# CH32H417WEU6-R0.net
KiCad netlist of a schematic drawn in Altium Designer
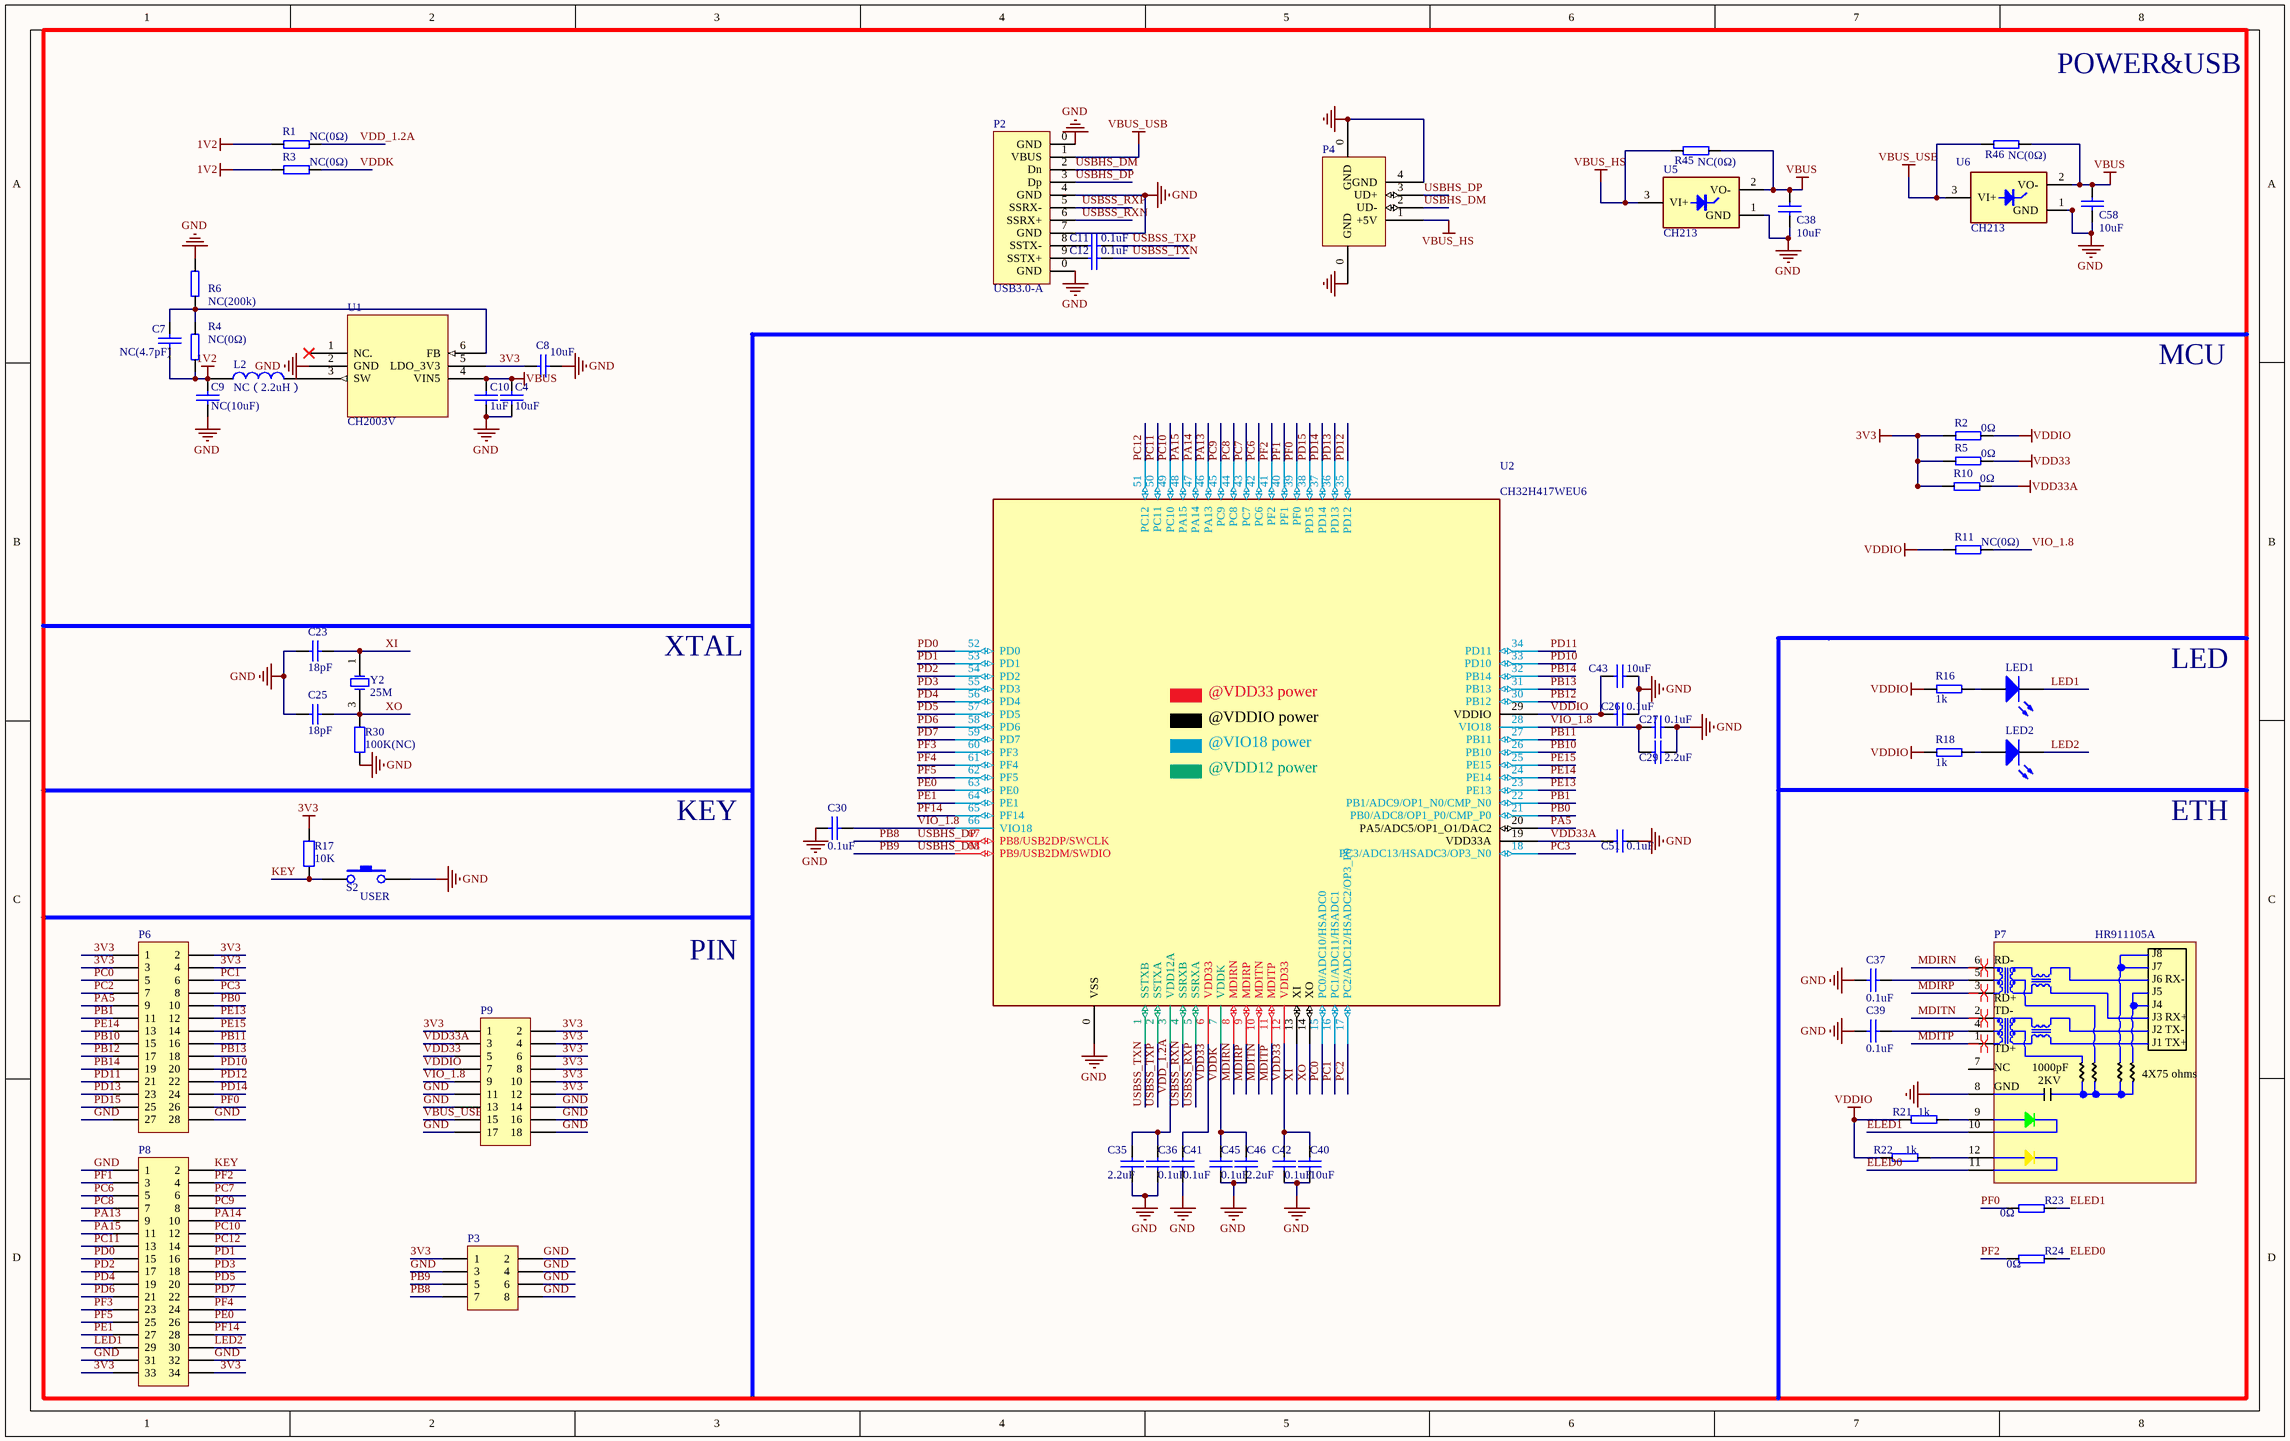
[diagram p0: CH32H417WEU6-R0.SchDoc]

(export (version "E")
  (design (tool "Eeschema 10.0.6"))
  (components
    (comp (ref "C4")
      (value "10uF")
      (footprint "0603_C")
      (description "Capacitor")
      (libsource (lib "*") (part "CAP"))
    )
    (comp (ref "C7")
      (value "NC(4.7pF)")
      (footprint "0402_C")
      (description "Capacitor")
      (libsource (lib "") (part "CAP_2"))
    )
    (comp (ref "C8")
      (value "10uF")
      (footprint "0603_C")
      (description "Capacitor")
      (libsource (lib "*") (part "CAP"))
    )
    (comp (ref "C9")
      (value "NC(10uF)")
      (footprint "0603_C")
      (description "Capacitor")
      (libsource (lib "*") (part "CAP"))
    )
    (comp (ref "C10")
      (value "1uF")
      (footprint "0402_C")
      (description "Capacitor")
      (libsource (lib "") (part "CAP_2"))
    )
    (comp (ref "C11")
      (value "0.1uF")
      (footprint "0402_C")
      (description "Capacitor")
      (libsource (lib "*") (part "CAP"))
    )
    (comp (ref "C12")
      (value "0.1uF")
      (footprint "0402_C")
      (description "Capacitor")
      (libsource (lib "*") (part "CAP"))
    )
    (comp (ref "C23")
      (value "18pF")
      (footprint "0402_C")
      (description "Capacitor")
      (libsource (lib "Miscellaneous Devices") (part "Cap"))
    )
    (comp (ref "C25")
      (value "18pF")
      (footprint "0402_C")
      (description "Capacitor")
      (libsource (lib "Miscellaneous Devices") (part "Cap"))
    )
    (comp (ref "C26")
      (value "0.1uF")
      (footprint "0402_C")
      (description "Capacitor")
      (libsource (lib "*") (part "CAP"))
    )
    (comp (ref "C27")
      (value "0.1uF")
      (footprint "0402_C")
      (description "Capacitor")
      (libsource (lib "*") (part "CAP"))
    )
    (comp (ref "C29")
      (value "2.2uF")
      (footprint "0402_C")
      (description "Capacitor")
      (libsource (lib "*") (part "CAP"))
    )
    (comp (ref "C30")
      (value "0.1uF")
      (footprint "0402_C")
      (description "Capacitor")
      (libsource (lib "*") (part "CAP"))
    )
    (comp (ref "C35")
      (value "2.2uF")
      (footprint "0402_C")
      (description "Capacitor")
      (libsource (lib "*") (part "CAP"))
    )
    (comp (ref "C36")
      (value "0.1uF")
      (footprint "0402_C")
      (description "Capacitor")
      (libsource (lib "*") (part "CAP"))
    )
    (comp (ref "C37")
      (value "0.1uF")
      (footprint "0402_C")
      (description "Capacitor")
      (libsource (lib "wch_sch_others") (part "CAP"))
    )
    (comp (ref "C38")
      (value "10uF")
      (footprint "0603_C")
      (description "Capacitor")
      (libsource (lib "") (part "CAP_1"))
    )
    (comp (ref "C39")
      (value "0.1uF")
      (footprint "0402_C")
      (description "Capacitor")
      (libsource (lib "wch_sch_others") (part "CAP"))
    )
    (comp (ref "C40")
      (value "10uF")
      (footprint "0402_C")
      (description "Capacitor")
      (libsource (lib "*") (part "CAP"))
    )
    (comp (ref "C41")
      (value "0.1uF")
      (footprint "0402_C")
      (description "Capacitor")
      (libsource (lib "*") (part "CAP"))
    )
    (comp (ref "C42")
      (value "0.1uF")
      (footprint "0402_C")
      (description "Capacitor")
      (libsource (lib "*") (part "CAP"))
    )
    (comp (ref "C43")
      (value "10uF")
      (footprint "0402_C")
      (description "Capacitor")
      (libsource (lib "*") (part "CAP"))
    )
    (comp (ref "C45")
      (value "0.1uF")
      (footprint "0402_C")
      (description "Capacitor")
      (libsource (lib "*") (part "CAP"))
    )
    (comp (ref "C46")
      (value "2.2uF")
      (footprint "0402_C")
      (description "Capacitor")
      (libsource (lib "*") (part "CAP"))
    )
    (comp (ref "C51")
      (value "0.1uF")
      (footprint "0402_C")
      (description "Capacitor")
      (libsource (lib "*") (part "CAP"))
    )
    (comp (ref "C58")
      (value "10uF")
      (footprint "0603_C")
      (description "Capacitor")
      (libsource (lib "") (part "CAP_1"))
    )
    (comp (ref "L2") (value "NC（2.2uH）") (footprint "CD32") (libsource (lib "*") (part "INDUCTOR")))
    (comp (ref "LED1")
      (value "LED2  blue")
      (footprint "0603+")
      (description "Typical INFRARED GaAs LED")
      (fields (field (name "PUBLISHER") "Altium Limited"))
      (libsource (lib "Miscellaneous Devices") (part "LED0"))
    )
    (comp (ref "LED2")
      (value "LED1   blue")
      (footprint "0603+")
      (description "Typical INFRARED GaAs LED")
      (fields (field (name "PUBLISHER") "Altium Limited"))
      (libsource (lib "Miscellaneous Devices") (part "LED0"))
    )
    (comp (ref "P2")
      (value "USB3.0-A")
      (footprint "USB3.0-A-Receptacle")
      (libsource (lib "wch_sch_others") (part "USB3.0-A"))
    )
    (comp (ref "P3")
      (value "HEADER 4x2")
      (footprint "MYPCB:IDC8-2.54mm")
      (description "Header, 4-Pin, Dual row")
      (libsource (lib "wch_sch_others") (part "HEADER 4x2"))
    )
    (comp (ref "P4")
      (value "USB_A")
      (footprint "USBAF")
      (description "USB Port")
      (libsource (lib "*") (part "USB"))
    )
    (comp (ref "P6")
      (value "HEADER 14x2")
      (footprint "MYPCB:IDC28-2.54MM")
      (description "Header, 14-Pin, Dual row")
      (libsource (lib "wch_sch_others") (part "HEADER 14x2"))
    )
    (comp (ref "P7") (value "HR911105A") (footprint "HR911105A") (libsource (lib "*") (part "HR911105A")))
    (comp (ref "P8")
      (value "HEADER 17x2")
      (footprint "MYPCB:IDC34-2.54MM")
      (description "Header, 17-Pin, Dual row")
      (libsource (lib "wch_sch_others") (part "HEADER 17x2"))
    )
    (comp (ref "P9")
      (value "HEADER 9x2")
      (footprint "MYPCB:IDC18-2.54MM")
      (description "Header, 9-Pin, Dual row")
      (libsource (lib "wch_sch_others") (part "HEADER 9x2"))
    )
    (comp (ref "R1") (value "NC(0Ω)") (footprint "0402") (libsource (lib "wch_sch_others") (part "RES")))
    (comp (ref "R2") (value "0Ω") (footprint "0402") (libsource (lib "wch_sch_others") (part "RES")))
    (comp (ref "R3") (value "NC(0Ω)") (footprint "0402") (libsource (lib "wch_sch_others") (part "RES")))
    (comp (ref "R4") (value "NC(0Ω)") (footprint "0402") (libsource (lib "wch_sch_others") (part "RES")))
    (comp (ref "R5") (value "0Ω") (footprint "0402") (libsource (lib "wch_sch_others") (part "RES")))
    (comp (ref "R6") (value "NC(200k)") (footprint "0402") (libsource (lib "wch_sch_others") (part "RES")))
    (comp (ref "R10") (value "0Ω") (footprint "0402") (libsource (lib "wch_sch_others") (part "RES")))
    (comp (ref "R11") (value "NC(0Ω)") (footprint "0402") (libsource (lib "wch_sch_others") (part "RES")))
    (comp (ref "R16") (value "1k") (footprint "0402") (libsource (lib "wch_sch_others") (part "RES")))
    (comp (ref "R17")
      (value "10K")
      (footprint "0402")
      (description "Resistor")
      (libsource (lib "Miscellaneous Devices") (part "Res2"))
    )
    (comp (ref "R18") (value "1k") (footprint "0402") (libsource (lib "wch_sch_others") (part "RES")))
    (comp (ref "R21") (value "1k") (footprint "0402") (libsource (lib "") (part "RES_1")))
    (comp (ref "R22") (value "1k") (footprint "0402") (libsource (lib "") (part "RES_1")))
    (comp (ref "R23") (value "0Ω") (footprint "0402") (libsource (lib "") (part "RES_1")))
    (comp (ref "R24") (value "0Ω") (footprint "0402") (libsource (lib "") (part "RES_1")))
    (comp (ref "R30")
      (value "100K(NC)")
      (footprint "0402")
      (description "Resistor")
      (libsource (lib "") (part "Res2_1"))
    )
    (comp (ref "R45") (value "NC(0Ω)") (footprint "0402") (libsource (lib "") (part "RES_1")))
    (comp (ref "R46") (value "NC(0Ω)") (footprint "0402") (libsource (lib "") (part "RES_1")))
    (comp (ref "S2")
      (value "USER")
      (footprint "SMD_6.1x3.65x2.5mm-KEY")
      (libsource (lib "wch_sch_others") (part "KEY1"))
    )
    (comp (ref "U1")
      (value "CH2003V")
      (footprint "SOT-23-6")
      (description "Step-Down DC-DC Converter, 5V input, FB 0.6V, 800mA output, with LDO 3.3V * 200mA")
      (libsource (lib "DHXXXSCH") (part "CH2003K"))
    )
    (comp (ref "U2")
      (value "CH32H417WEU6")
      (footprint "QFN68_8X8")
      (description "RISC-V FPU HD-MCU, 400MHz, USB3.0, 100M Ethernet, DVP, SDMMC, QSPI, OPA, ADC, DAC")
      (libsource (lib "DHXXXSCH") (part "CH32H417WEU6"))
    )
    (comp (ref "U5")
      (value "CH213")
      (footprint "SOT-23-3")
      (description "Ideal Diode 5V*1A")
      (libsource (lib "CHXXX") (part "CH213E"))
    )
    (comp (ref "U6")
      (value "CH213")
      (footprint "SOT-23-3")
      (description "Ideal Diode 5V*1A")
      (libsource (lib "CHXXX") (part "CH213E"))
    )
    (comp (ref "Y2")
      (value "25M")
      (footprint "XT3225")
      (description "Crystal Oscillator")
      (fields (field (name "PUBLISHER") "Altium Limited"))
      (libsource (lib "Miscellaneous Devices") (part "XTAL"))
    )
  )
  (nets
    (net (code "1") (name "/ELED0") (class "Default")
      (node (ref "P7") (pin "11") (pintype "passive"))
      (node (ref "R24") (pin "2") (pintype "passive"))
    )
    (net (code "2") (name "/ELED1") (class "Default")
      (node (ref "P7") (pin "10") (pintype "passive"))
      (node (ref "R23") (pin "2") (pintype "passive"))
    )
    (net (code "3") (name "/KEY") (class "Default")
      (node (ref "P8") (pin "2") (pinfunction "2_2") (pintype "passive"))
      (node (ref "R17") (pin "2") (pinfunction "2_2") (pintype "passive"))
      (node (ref "S2") (pin "1") (pinfunction "1_1") (pintype "passive"))
    )
    (net (code "4") (name "/LED1") (class "Default")
      (node (ref "LED1") (pin "2") (pinfunction "K_2") (pintype "passive"))
      (node (ref "P8") (pin "29") (pinfunction "29_29") (pintype "passive"))
    )
    (net (code "5") (name "/LED2") (class "Default")
      (node (ref "LED2") (pin "2") (pinfunction "K_2") (pintype "passive"))
      (node (ref "P8") (pin "30") (pinfunction "30_30") (pintype "passive"))
    )
    (net (code "6") (name "/MDIRN") (class "Default")
      (node (ref "P7") (pin "6") (pintype "passive"))
      (node (ref "U2") (pin "8") (pinfunction "MDIRN_8") (pintype "bidirectional"))
    )
    (net (code "7") (name "/MDIRP") (class "Default")
      (node (ref "P7") (pin "3") (pintype "passive"))
      (node (ref "U2") (pin "9") (pinfunction "MDIRP_9") (pintype "bidirectional"))
    )
    (net (code "8") (name "/MDITN") (class "Default")
      (node (ref "P7") (pin "2") (pintype "passive"))
      (node (ref "U2") (pin "10") (pinfunction "MDITN_10") (pintype "bidirectional"))
    )
    (net (code "9") (name "/MDITP") (class "Default")
      (node (ref "P7") (pin "1") (pintype "passive"))
      (node (ref "U2") (pin "11") (pinfunction "MDITP_11") (pintype "bidirectional"))
    )
    (net (code "10") (name "/PA5") (class "Default")
      (node (ref "P6") (pin "9") (pinfunction "9_9") (pintype "passive"))
      (node (ref "U2") (pin "20") (pinfunction "PA5/ADC5/OP1_O1/DAC2_20") (pintype "bidirectional"))
    )
    (net (code "11") (name "/PA13") (class "Default")
      (node (ref "P8") (pin "9") (pinfunction "9_9") (pintype "passive"))
      (node (ref "U2") (pin "46") (pinfunction "PA13_46") (pintype "bidirectional"))
    )
    (net (code "12") (name "/PA14") (class "Default")
      (node (ref "P8") (pin "10") (pinfunction "10_10") (pintype "passive"))
      (node (ref "U2") (pin "47") (pinfunction "PA14_47") (pintype "bidirectional"))
    )
    (net (code "13") (name "/PA15") (class "Default")
      (node (ref "P8") (pin "11") (pinfunction "11_11") (pintype "passive"))
      (node (ref "U2") (pin "48") (pinfunction "PA15_48") (pintype "bidirectional"))
    )
    (net (code "14") (name "/PB0") (class "Default")
      (node (ref "P6") (pin "10") (pinfunction "10_10") (pintype "passive"))
      (node (ref "U2") (pin "21") (pinfunction "PB0/ADC8/OP1_P0/CMP_P0_21") (pintype "bidirectional"))
    )
    (net (code "15") (name "/PB1") (class "Default")
      (node (ref "P6") (pin "11") (pinfunction "11_11") (pintype "passive"))
      (node (ref "U2") (pin "22") (pinfunction "PB1/ADC9/OP1_N0/CMP_N0_22") (pintype "bidirectional"))
    )
    (net (code "16") (name "/PB8") (class "Default")
      (node (ref "P2") (pin "3") (pinfunction "Dp_3") (pintype "passive"))
      (node (ref "P3") (pin "7") (pinfunction "7_7") (pintype "passive"))
      (node (ref "P4") (pin "3") (pinfunction "UD+_3") (pintype "bidirectional"))
      (node (ref "U2") (pin "67") (pinfunction "PB8/USB2DP/SWCLK_67") (pintype "bidirectional"))
    )
    (net (code "17") (name "/PB9") (class "Default")
      (node (ref "P2") (pin "2") (pinfunction "Dn_2") (pintype "passive"))
      (node (ref "P3") (pin "5") (pinfunction "5_5") (pintype "passive"))
      (node (ref "P4") (pin "2") (pinfunction "UD-_2") (pintype "bidirectional"))
      (node (ref "U2") (pin "68") (pinfunction "PB9/USB2DM/SWDIO_68") (pintype "bidirectional"))
    )
    (net (code "18") (name "/PB10") (class "Default")
      (node (ref "P6") (pin "15") (pinfunction "15_15") (pintype "passive"))
      (node (ref "U2") (pin "26") (pinfunction "PB10_26") (pintype "bidirectional"))
    )
    (net (code "19") (name "/PB11") (class "Default")
      (node (ref "P6") (pin "16") (pinfunction "16_16") (pintype "passive"))
      (node (ref "U2") (pin "27") (pinfunction "PB11_27") (pintype "bidirectional"))
    )
    (net (code "20") (name "/PB12") (class "Default")
      (node (ref "P6") (pin "17") (pinfunction "17_17") (pintype "passive"))
      (node (ref "U2") (pin "30") (pinfunction "PB12_30") (pintype "bidirectional"))
    )
    (net (code "21") (name "/PB13") (class "Default")
      (node (ref "P6") (pin "18") (pinfunction "18_18") (pintype "passive"))
      (node (ref "U2") (pin "31") (pinfunction "PB13_31") (pintype "bidirectional"))
    )
    (net (code "22") (name "/PB14") (class "Default")
      (node (ref "P6") (pin "19") (pinfunction "19_19") (pintype "passive"))
      (node (ref "U2") (pin "32") (pinfunction "PB14_32") (pintype "bidirectional"))
    )
    (net (code "23") (name "/PC0") (class "Default")
      (node (ref "P6") (pin "5") (pinfunction "5_5") (pintype "passive"))
      (node (ref "U2") (pin "15") (pinfunction "PC0/ADC10/HSADC0_15") (pintype "bidirectional"))
    )
    (net (code "24") (name "/PC1") (class "Default")
      (node (ref "P6") (pin "6") (pinfunction "6_6") (pintype "passive"))
      (node (ref "U2") (pin "16") (pinfunction "PC1/ADC11/HSADC1_16") (pintype "bidirectional"))
    )
    (net (code "25") (name "/PC2") (class "Default")
      (node (ref "P6") (pin "7") (pinfunction "7_7") (pintype "passive"))
      (node (ref "U2") (pin "17") (pinfunction "PC2/ADC12/HSADC2/OP3_P0_17") (pintype "bidirectional"))
    )
    (net (code "26") (name "/PC3") (class "Default")
      (node (ref "P6") (pin "8") (pinfunction "8_8") (pintype "passive"))
      (node (ref "U2") (pin "18") (pinfunction "PC3/ADC13/HSADC3/OP3_N0_18") (pintype "bidirectional"))
    )
    (net (code "27") (name "/PC6") (class "Default")
      (node (ref "P8") (pin "5") (pinfunction "5_5") (pintype "passive"))
      (node (ref "U2") (pin "42") (pinfunction "PC6_42") (pintype "bidirectional"))
    )
    (net (code "28") (name "/PC7") (class "Default")
      (node (ref "P8") (pin "6") (pinfunction "6_6") (pintype "passive"))
      (node (ref "U2") (pin "43") (pinfunction "PC7_43") (pintype "bidirectional"))
    )
    (net (code "29") (name "/PC8") (class "Default")
      (node (ref "P8") (pin "7") (pinfunction "7_7") (pintype "passive"))
      (node (ref "U2") (pin "44") (pinfunction "PC8_44") (pintype "bidirectional"))
    )
    (net (code "30") (name "/PC9") (class "Default")
      (node (ref "P8") (pin "8") (pinfunction "8_8") (pintype "passive"))
      (node (ref "U2") (pin "45") (pinfunction "PC9_45") (pintype "bidirectional"))
    )
    (net (code "31") (name "/PC10") (class "Default")
      (node (ref "P8") (pin "12") (pinfunction "12_12") (pintype "passive"))
      (node (ref "U2") (pin "49") (pinfunction "PC10_49") (pintype "bidirectional"))
    )
    (net (code "32") (name "/PC11") (class "Default")
      (node (ref "P8") (pin "13") (pinfunction "13_13") (pintype "passive"))
      (node (ref "U2") (pin "50") (pinfunction "PC11_50") (pintype "bidirectional"))
    )
    (net (code "33") (name "/PC12") (class "Default")
      (node (ref "P8") (pin "14") (pinfunction "14_14") (pintype "passive"))
      (node (ref "U2") (pin "51") (pinfunction "PC12_51") (pintype "bidirectional"))
    )
    (net (code "34") (name "/PD0") (class "Default")
      (node (ref "P8") (pin "15") (pinfunction "15_15") (pintype "passive"))
      (node (ref "U2") (pin "52") (pinfunction "PD0_52") (pintype "bidirectional"))
    )
    (net (code "35") (name "/PD1") (class "Default")
      (node (ref "P8") (pin "16") (pinfunction "16_16") (pintype "passive"))
      (node (ref "U2") (pin "53") (pinfunction "PD1_53") (pintype "bidirectional"))
    )
    (net (code "36") (name "/PD2") (class "Default")
      (node (ref "P8") (pin "17") (pinfunction "17_17") (pintype "passive"))
      (node (ref "U2") (pin "54") (pinfunction "PD2_54") (pintype "bidirectional"))
    )
    (net (code "37") (name "/PD3") (class "Default")
      (node (ref "P8") (pin "18") (pinfunction "18_18") (pintype "passive"))
      (node (ref "U2") (pin "55") (pinfunction "PD3_55") (pintype "bidirectional"))
    )
    (net (code "38") (name "/PD4") (class "Default")
      (node (ref "P8") (pin "19") (pinfunction "19_19") (pintype "passive"))
      (node (ref "U2") (pin "56") (pinfunction "PD4_56") (pintype "bidirectional"))
    )
    (net (code "39") (name "/PD5") (class "Default")
      (node (ref "P8") (pin "20") (pinfunction "20_20") (pintype "passive"))
      (node (ref "U2") (pin "57") (pinfunction "PD5_57") (pintype "bidirectional"))
    )
    (net (code "40") (name "/PD6") (class "Default")
      (node (ref "P8") (pin "21") (pinfunction "21_21") (pintype "passive"))
      (node (ref "U2") (pin "58") (pinfunction "PD6_58") (pintype "bidirectional"))
    )
    (net (code "41") (name "/PD7") (class "Default")
      (node (ref "P8") (pin "22") (pinfunction "22_22") (pintype "passive"))
      (node (ref "U2") (pin "59") (pinfunction "PD7_59") (pintype "bidirectional"))
    )
    (net (code "42") (name "/PD10") (class "Default")
      (node (ref "P6") (pin "20") (pinfunction "20_20") (pintype "passive"))
      (node (ref "U2") (pin "33") (pinfunction "PD10_33") (pintype "bidirectional"))
    )
    (net (code "43") (name "/PD11") (class "Default")
      (node (ref "P6") (pin "21") (pinfunction "21_21") (pintype "passive"))
      (node (ref "U2") (pin "34") (pinfunction "PD11_34") (pintype "bidirectional"))
    )
    (net (code "44") (name "/PD12") (class "Default")
      (node (ref "P6") (pin "22") (pinfunction "22_22") (pintype "passive"))
      (node (ref "U2") (pin "35") (pinfunction "PD12_35") (pintype "bidirectional"))
    )
    (net (code "45") (name "/PD13") (class "Default")
      (node (ref "P6") (pin "23") (pinfunction "23_23") (pintype "passive"))
      (node (ref "U2") (pin "36") (pinfunction "PD13_36") (pintype "bidirectional"))
    )
    (net (code "46") (name "/PD14") (class "Default")
      (node (ref "P6") (pin "24") (pinfunction "24_24") (pintype "passive"))
      (node (ref "U2") (pin "37") (pinfunction "PD14_37") (pintype "bidirectional"))
    )
    (net (code "47") (name "/PD15") (class "Default")
      (node (ref "P6") (pin "25") (pinfunction "25_25") (pintype "passive"))
      (node (ref "U2") (pin "38") (pinfunction "PD15_38") (pintype "bidirectional"))
    )
    (net (code "48") (name "/PE0") (class "Default")
      (node (ref "P8") (pin "26") (pinfunction "26_26") (pintype "passive"))
      (node (ref "U2") (pin "63") (pinfunction "PE0_63") (pintype "bidirectional"))
    )
    (net (code "49") (name "/PE1") (class "Default")
      (node (ref "P8") (pin "27") (pinfunction "27_27") (pintype "passive"))
      (node (ref "U2") (pin "64") (pinfunction "PE1_64") (pintype "bidirectional"))
    )
    (net (code "50") (name "/PE13") (class "Default")
      (node (ref "P6") (pin "12") (pinfunction "12_12") (pintype "passive"))
      (node (ref "U2") (pin "23") (pinfunction "PE13_23") (pintype "bidirectional"))
    )
    (net (code "51") (name "/PE14") (class "Default")
      (node (ref "P6") (pin "13") (pinfunction "13_13") (pintype "passive"))
      (node (ref "U2") (pin "24") (pinfunction "PE14_24") (pintype "bidirectional"))
    )
    (net (code "52") (name "/PE15") (class "Default")
      (node (ref "P6") (pin "14") (pinfunction "14_14") (pintype "passive"))
      (node (ref "U2") (pin "25") (pinfunction "PE15_25") (pintype "bidirectional"))
    )
    (net (code "53") (name "/PF0") (class "Default")
      (node (ref "P6") (pin "26") (pinfunction "26_26") (pintype "passive"))
      (node (ref "R23") (pin "1") (pintype "passive"))
      (node (ref "U2") (pin "39") (pinfunction "PF0_39") (pintype "bidirectional"))
    )
    (net (code "54") (name "/PF1") (class "Default")
      (node (ref "P8") (pin "3") (pinfunction "3_3") (pintype "passive"))
      (node (ref "U2") (pin "40") (pinfunction "PF1_40") (pintype "bidirectional"))
    )
    (net (code "55") (name "/PF2") (class "Default")
      (node (ref "P8") (pin "4") (pinfunction "4_4") (pintype "passive"))
      (node (ref "R24") (pin "1") (pintype "passive"))
      (node (ref "U2") (pin "41") (pinfunction "PF2_41") (pintype "bidirectional"))
    )
    (net (code "56") (name "/PF3") (class "Default")
      (node (ref "P8") (pin "23") (pinfunction "23_23") (pintype "passive"))
      (node (ref "U2") (pin "60") (pinfunction "PF3_60") (pintype "bidirectional"))
    )
    (net (code "57") (name "/PF4") (class "Default")
      (node (ref "P8") (pin "24") (pinfunction "24_24") (pintype "passive"))
      (node (ref "U2") (pin "61") (pinfunction "PF4_61") (pintype "bidirectional"))
    )
    (net (code "58") (name "/PF5") (class "Default")
      (node (ref "P8") (pin "25") (pinfunction "25_25") (pintype "passive"))
      (node (ref "U2") (pin "62") (pinfunction "PF5_62") (pintype "bidirectional"))
    )
    (net (code "59") (name "/PF14") (class "Default")
      (node (ref "P8") (pin "28") (pinfunction "28_28") (pintype "passive"))
      (node (ref "U2") (pin "65") (pinfunction "PF14_65") (pintype "bidirectional"))
    )
    (net (code "60") (name "/USBSS_RXN") (class "Default")
      (node (ref "P2") (pin "6") (pinfunction "SSRX+_6") (pintype "passive"))
      (node (ref "U2") (pin "4") (pinfunction "SSRXB_4") (pintype "bidirectional"))
    )
    (net (code "61") (name "/USBSS_RXP") (class "Default")
      (node (ref "P2") (pin "5") (pinfunction "SSRX-_5") (pintype "passive"))
      (node (ref "U2") (pin "5") (pinfunction "SSRXA_5") (pintype "bidirectional"))
    )
    (net (code "62") (name "/USBSS_TXN") (class "Default")
      (node (ref "C12") (pin "2") (pinfunction "2_2") (pintype "passive"))
      (node (ref "U2") (pin "1") (pinfunction "SSTXB_1") (pintype "bidirectional"))
    )
    (net (code "63") (name "/USBSS_TXP") (class "Default")
      (node (ref "C11") (pin "2") (pinfunction "2_2") (pintype "passive"))
      (node (ref "U2") (pin "2") (pinfunction "SSTXA_2") (pintype "bidirectional"))
    )
    (net (code "64") (name "/VDDK") (class "Default")
      (node (ref "C45") (pin "2") (pinfunction "2_2") (pintype "passive"))
      (node (ref "C46") (pin "1") (pinfunction "1_1") (pintype "passive"))
      (node (ref "R3") (pin "1") (pintype "passive"))
      (node (ref "U2") (pin "7") (pinfunction "VDDK_7") (pintype "power_in"))
    )
    (net (code "65") (name "/VDD_1.2A") (class "Default")
      (node (ref "C35") (pin "2") (pinfunction "2_2") (pintype "passive"))
      (node (ref "C36") (pin "2") (pinfunction "2_2") (pintype "passive"))
      (node (ref "R1") (pin "1") (pintype "passive"))
      (node (ref "U2") (pin "3") (pinfunction "VDD12A_3") (pintype "power_in"))
    )
    (net (code "66") (name "/VIO_1.8") (class "Default")
      (node (ref "C27") (pin "1") (pinfunction "1_1") (pintype "passive"))
      (node (ref "C29") (pin "2") (pinfunction "2_2") (pintype "passive"))
      (node (ref "C30") (pin "1") (pinfunction "1_1") (pintype "passive"))
      (node (ref "P9") (pin "9") (pinfunction "9_9") (pintype "passive"))
      (node (ref "R11") (pin "1") (pintype "passive"))
      (node (ref "U2") (pin "28") (pinfunction "VIO18_28") (pintype "power_in"))
      (node (ref "U2") (pin "66") (pinfunction "VIO18_66") (pintype "power_in"))
    )
    (net (code "67") (name "/XI") (class "Default")
      (node (ref "C23") (pin "2") (pinfunction "2_2") (pintype "passive"))
      (node (ref "U2") (pin "13") (pinfunction "XI_13") (pintype "bidirectional"))
      (node (ref "Y2") (pin "1") (pinfunction "OSC1_1") (pintype "passive"))
    )
    (net (code "68") (name "/XO") (class "Default")
      (node (ref "C25") (pin "2") (pinfunction "2_2") (pintype "passive"))
      (node (ref "R30") (pin "2") (pinfunction "2_2") (pintype "passive"))
      (node (ref "U2") (pin "14") (pinfunction "XO_14") (pintype "bidirectional"))
      (node (ref "Y2") (pin "3") (pinfunction "OSC2_3") (pintype "passive"))
    )
    (net (code "69") (name "1V2") (class "Default")
      (node (ref "C7") (pin "1") (pinfunction "1_1") (pintype "passive"))
      (node (ref "C9") (pin "2") (pinfunction "2_2") (pintype "passive"))
      (node (ref "L2") (pin "2") (pinfunction "2_2") (pintype "passive"))
      (node (ref "R1") (pin "2") (pintype "passive"))
      (node (ref "R3") (pin "2") (pintype "passive"))
      (node (ref "R4") (pin "1") (pintype "passive"))
    )
    (net (code "70") (name "3V3") (class "Default")
      (node (ref "C8") (pin "2") (pinfunction "2_2") (pintype "passive"))
      (node (ref "P3") (pin "1") (pinfunction "1_1") (pintype "passive"))
      (node (ref "P6") (pin "1") (pinfunction "1_1") (pintype "passive"))
      (node (ref "P6") (pin "2") (pinfunction "2_2") (pintype "passive"))
      (node (ref "P6") (pin "3") (pinfunction "3_3") (pintype "passive"))
      (node (ref "P6") (pin "4") (pinfunction "4_4") (pintype "passive"))
      (node (ref "P8") (pin "33") (pinfunction "33_33") (pintype "passive"))
      (node (ref "P8") (pin "34") (pinfunction "34_34") (pintype "passive"))
      (node (ref "P9") (pin "1") (pinfunction "1_1") (pintype "passive"))
      (node (ref "P9") (pin "10") (pinfunction "10_10") (pintype "passive"))
      (node (ref "P9") (pin "12") (pinfunction "12_12") (pintype "passive"))
      (node (ref "P9") (pin "2") (pinfunction "2_2") (pintype "passive"))
      (node (ref "P9") (pin "4") (pinfunction "4_4") (pintype "passive"))
      (node (ref "P9") (pin "6") (pinfunction "6_6") (pintype "passive"))
      (node (ref "P9") (pin "8") (pinfunction "8_8") (pintype "passive"))
      (node (ref "R10") (pin "2") (pintype "passive"))
      (node (ref "R17") (pin "1") (pinfunction "1_1") (pintype "passive"))
      (node (ref "R2") (pin "2") (pintype "passive"))
      (node (ref "R5") (pin "2") (pintype "passive"))
      (node (ref "U1") (pin "5") (pinfunction "LDO_3V3_5") (pintype "power_in"))
    )
    (net (code "71") (name "GND") (class "Default")
      (node (ref "C10") (pin "1") (pinfunction "1_1") (pintype "passive"))
      (node (ref "C23") (pin "1") (pinfunction "1_1") (pintype "passive"))
      (node (ref "C25") (pin "1") (pinfunction "1_1") (pintype "passive"))
      (node (ref "C26") (pin "2") (pinfunction "2_2") (pintype "passive"))
      (node (ref "C27") (pin "2") (pinfunction "2_2") (pintype "passive"))
      (node (ref "C29") (pin "1") (pinfunction "1_1") (pintype "passive"))
      (node (ref "C30") (pin "2") (pinfunction "2_2") (pintype "passive"))
      (node (ref "C35") (pin "1") (pinfunction "1_1") (pintype "passive"))
      (node (ref "C36") (pin "1") (pinfunction "1_1") (pintype "passive"))
      (node (ref "C37") (pin "1") (pinfunction "1_1") (pintype "passive"))
      (node (ref "C38") (pin "2") (pinfunction "2_2") (pintype "passive"))
      (node (ref "C39") (pin "1") (pinfunction "1_1") (pintype "passive"))
      (node (ref "C4") (pin "1") (pinfunction "1_1") (pintype "passive"))
      (node (ref "C40") (pin "1") (pinfunction "1_1") (pintype "passive"))
      (node (ref "C41") (pin "1") (pinfunction "1_1") (pintype "passive"))
      (node (ref "C42") (pin "1") (pinfunction "1_1") (pintype "passive"))
      (node (ref "C43") (pin "1") (pinfunction "1_1") (pintype "passive"))
      (node (ref "C45") (pin "1") (pinfunction "1_1") (pintype "passive"))
      (node (ref "C46") (pin "2") (pinfunction "2_2") (pintype "passive"))
      (node (ref "C51") (pin "1") (pinfunction "1_1") (pintype "passive"))
      (node (ref "C58") (pin "2") (pinfunction "2_2") (pintype "passive"))
      (node (ref "C8") (pin "1") (pinfunction "1_1") (pintype "passive"))
      (node (ref "C9") (pin "1") (pinfunction "1_1") (pintype "passive"))
      (node (ref "P2") (pin "0") (pinfunction "GND_0") (pintype "passive"))
      (node (ref "P2") (pin "4") (pinfunction "GND_4") (pintype "passive"))
      (node (ref "P2") (pin "7") (pinfunction "GND_7") (pintype "passive"))
      (node (ref "P3") (pin "2") (pinfunction "2_2") (pintype "passive"))
      (node (ref "P3") (pin "3") (pinfunction "3_3") (pintype "passive"))
      (node (ref "P3") (pin "4") (pinfunction "4_4") (pintype "passive"))
      (node (ref "P3") (pin "6") (pinfunction "6_6") (pintype "passive"))
      (node (ref "P3") (pin "8") (pinfunction "8_8") (pintype "passive"))
      (node (ref "P4") (pin "0") (pinfunction "GND_0") (pintype "power_in"))
      (node (ref "P4") (pin "4") (pinfunction "GND_4") (pintype "power_in"))
      (node (ref "P6") (pin "27") (pinfunction "27_27") (pintype "passive"))
      (node (ref "P6") (pin "28") (pinfunction "28_28") (pintype "passive"))
      (node (ref "P7") (pin "8") (pintype "passive"))
      (node (ref "P8") (pin "1") (pinfunction "1_1") (pintype "passive"))
      (node (ref "P8") (pin "31") (pinfunction "31_31") (pintype "passive"))
      (node (ref "P8") (pin "32") (pinfunction "32_32") (pintype "passive"))
      (node (ref "P9") (pin "11") (pinfunction "11_11") (pintype "passive"))
      (node (ref "P9") (pin "13") (pinfunction "13_13") (pintype "passive"))
      (node (ref "P9") (pin "14") (pinfunction "14_14") (pintype "passive"))
      (node (ref "P9") (pin "16") (pinfunction "16_16") (pintype "passive"))
      (node (ref "P9") (pin "17") (pinfunction "17_17") (pintype "passive"))
      (node (ref "P9") (pin "18") (pinfunction "18_18") (pintype "passive"))
      (node (ref "R30") (pin "1") (pinfunction "1_1") (pintype "passive"))
      (node (ref "R6") (pin "2") (pintype "passive"))
      (node (ref "S2") (pin "2") (pinfunction "2_2") (pintype "passive"))
      (node (ref "U1") (pin "2") (pinfunction "GND_2") (pintype "power_in"))
      (node (ref "U2") (pin "0") (pinfunction "VSS_0") (pintype "power_in"))
      (node (ref "U5") (pin "1") (pinfunction "GND_1") (pintype "power_in"))
      (node (ref "U6") (pin "1") (pinfunction "GND_1") (pintype "power_in"))
    )
    (net (code "72") (name "Net-(C37-Pad2)") (class "Default")
      (node (ref "C37") (pin "2") (pinfunction "2_2") (pintype "passive"))
      (node (ref "P7") (pin "5") (pintype "passive"))
    )
    (net (code "73") (name "Net-(C39-Pad2)") (class "Default")
      (node (ref "C39") (pin "2") (pinfunction "2_2") (pintype "passive"))
      (node (ref "P7") (pin "4") (pintype "passive"))
    )
    (net (code "74") (name "Net-(LED1-A)") (class "Default")
      (node (ref "LED1") (pin "1") (pinfunction "A_1") (pintype "passive"))
      (node (ref "R16") (pin "2") (pintype "passive"))
    )
    (net (code "75") (name "Net-(LED2-A)") (class "Default")
      (node (ref "LED2") (pin "1") (pinfunction "A_1") (pintype "passive"))
      (node (ref "R18") (pin "2") (pintype "passive"))
    )
    (net (code "76") (name "Net-(P2-SSTX+)") (class "Default")
      (node (ref "C12") (pin "1") (pinfunction "1_1") (pintype "passive"))
      (node (ref "P2") (pin "9") (pinfunction "SSTX+_9") (pintype "passive"))
    )
    (net (code "77") (name "Net-(P2-SSTX-)") (class "Default")
      (node (ref "C11") (pin "1") (pinfunction "1_1") (pintype "passive"))
      (node (ref "P2") (pin "8") (pinfunction "SSTX-_8") (pintype "passive"))
    )
    (net (code "78") (name "Net-(P7-Pad9)") (class "Default")
      (node (ref "P7") (pin "9") (pintype "passive"))
      (node (ref "R21") (pin "2") (pintype "passive"))
    )
    (net (code "79") (name "Net-(P7-Pad12)") (class "Default")
      (node (ref "P7") (pin "12") (pintype "passive"))
      (node (ref "R22") (pin "2") (pintype "passive"))
    )
    (net (code "80") (name "Net-(U1-FB)") (class "Default")
      (node (ref "C7") (pin "2") (pinfunction "2_2") (pintype "passive"))
      (node (ref "R4") (pin "2") (pintype "passive"))
      (node (ref "R6") (pin "1") (pintype "passive"))
      (node (ref "U1") (pin "6") (pinfunction "FB_6") (pintype "input"))
    )
    (net (code "81") (name "Net-(U1-SW)") (class "Default")
      (node (ref "L2") (pin "1") (pinfunction "1_1") (pintype "passive"))
      (node (ref "U1") (pin "3") (pinfunction "SW_3") (pintype "output"))
    )
    (net (code "82") (name "VBUS") (class "Default")
      (node (ref "C10") (pin "2") (pinfunction "2_2") (pintype "passive"))
      (node (ref "C38") (pin "1") (pinfunction "1_1") (pintype "passive"))
      (node (ref "C4") (pin "2") (pinfunction "2_2") (pintype "passive"))
      (node (ref "C58") (pin "1") (pinfunction "1_1") (pintype "passive"))
      (node (ref "R45") (pin "1") (pintype "passive"))
      (node (ref "R46") (pin "1") (pintype "passive"))
      (node (ref "U1") (pin "4") (pinfunction "VIN5_4") (pintype "power_in"))
      (node (ref "U5") (pin "2") (pinfunction "VO-_2") (pintype "power_in"))
      (node (ref "U6") (pin "2") (pinfunction "VO-_2") (pintype "power_in"))
    )
    (net (code "83") (name "VBUS_HS") (class "Default")
      (node (ref "P4") (pin "1") (pinfunction "+5V_1") (pintype "power_in"))
      (node (ref "R45") (pin "2") (pintype "passive"))
      (node (ref "U5") (pin "3") (pinfunction "VI+_3") (pintype "power_in"))
    )
    (net (code "84") (name "VBUS_USB") (class "Default")
      (node (ref "P2") (pin "1") (pinfunction "VBUS_1") (pintype "passive"))
      (node (ref "P9") (pin "15") (pinfunction "15_15") (pintype "passive"))
      (node (ref "R46") (pin "2") (pintype "passive"))
      (node (ref "U6") (pin "3") (pinfunction "VI+_3") (pintype "power_in"))
    )
    (net (code "85") (name "VDD33") (class "Default")
      (node (ref "C40") (pin "2") (pinfunction "2_2") (pintype "passive"))
      (node (ref "C41") (pin "2") (pinfunction "2_2") (pintype "passive"))
      (node (ref "C42") (pin "2") (pinfunction "2_2") (pintype "passive"))
      (node (ref "P9") (pin "5") (pinfunction "5_5") (pintype "passive"))
      (node (ref "R5") (pin "1") (pintype "passive"))
      (node (ref "U2") (pin "12") (pinfunction "VDD33_12") (pintype "power_in"))
      (node (ref "U2") (pin "6") (pinfunction "VDD33_6") (pintype "power_in"))
    )
    (net (code "86") (name "VDD33A") (class "Default")
      (node (ref "C51") (pin "2") (pinfunction "2_2") (pintype "passive"))
      (node (ref "P9") (pin "3") (pinfunction "3_3") (pintype "passive"))
      (node (ref "R10") (pin "1") (pintype "passive"))
      (node (ref "U2") (pin "19") (pinfunction "VDD33A_19") (pintype "power_in"))
    )
    (net (code "87") (name "VDDIO") (class "Default")
      (node (ref "C26") (pin "1") (pinfunction "1_1") (pintype "passive"))
      (node (ref "C43") (pin "2") (pinfunction "2_2") (pintype "passive"))
      (node (ref "P9") (pin "7") (pinfunction "7_7") (pintype "passive"))
      (node (ref "R11") (pin "2") (pintype "passive"))
      (node (ref "R16") (pin "1") (pintype "passive"))
      (node (ref "R18") (pin "1") (pintype "passive"))
      (node (ref "R2") (pin "1") (pintype "passive"))
      (node (ref "R21") (pin "1") (pintype "passive"))
      (node (ref "R22") (pin "1") (pintype "passive"))
      (node (ref "U2") (pin "29") (pinfunction "VDDIO_29") (pintype "power_in"))
    )
    (net (code "88") (name "unconnected-(P7-Pad7)") (class "Default")
      (node (ref "P7") (pin "7") (pintype "passive"))
    )
    (net (code "89") (name "unconnected-(U1-NC.-Pad1)") (class "Default")
      (node (ref "U1") (pin "1") (pinfunction "NC._1") (pintype "passive+no_connect"))
    )
  )
)
